# Main.net
KiCad netlist of a schematic drawn in Altium Designer
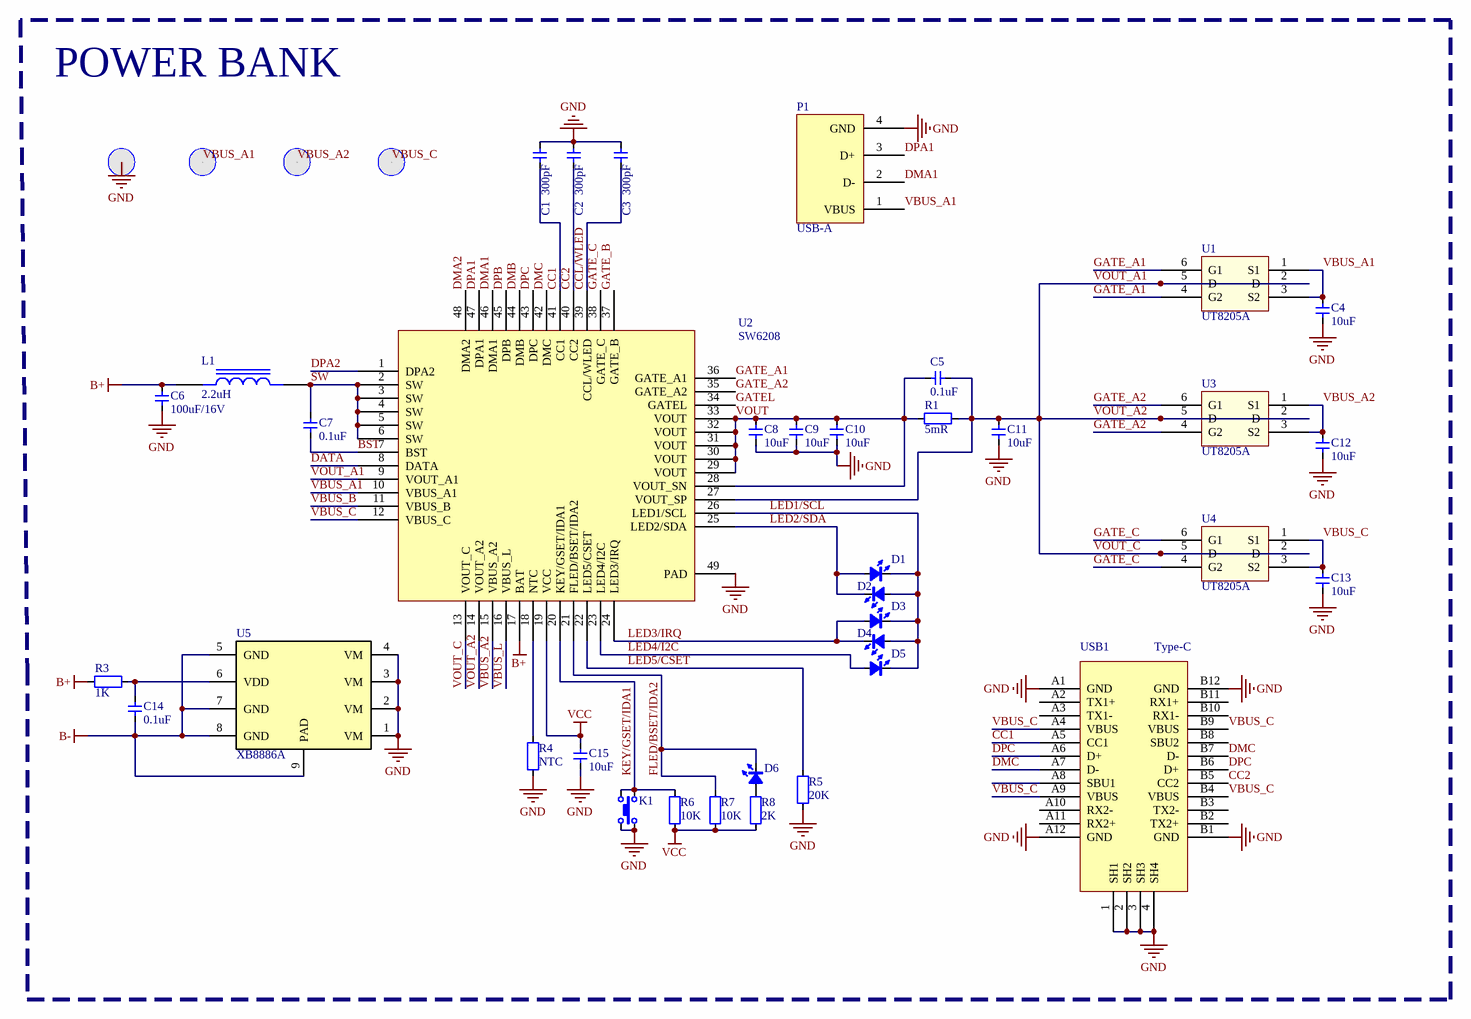
[diagram p0: Main.SchDoc]

(export (version "E")
  (design (tool "Eeschema 10.0.6"))
  (components
    (comp (ref "C1")
      (value "300pF")
      (footprint "CAP_0402")
      (description "Capacitor")
      (libsource (lib "MyPcbLib") (part "电容-0402"))
    )
    (comp (ref "C2")
      (value "300pF")
      (footprint "CAP_0402")
      (description "Capacitor")
      (libsource (lib "MyPcbLib") (part "电容-0402"))
    )
    (comp (ref "C3")
      (value "300pF")
      (footprint "CAP_0402")
      (description "Capacitor")
      (libsource (lib "MyPcbLib") (part "电容-0402"))
    )
    (comp (ref "C4")
      (value "10uF")
      (footprint "0603-CAP")
      (description "Capacitor")
      (libsource (lib "MyPcbLib") (part "电容-0603"))
    )
    (comp (ref "C5")
      (value "0.1uF")
      (footprint "CAP_0402")
      (description "Capacitor")
      (libsource (lib "MyPcbLib") (part "电容-0402"))
    )
    (comp (ref "C6")
      (value "100uF/16V")
      (footprint "1206-CAP")
      (description "Capacitor")
      (libsource (lib "MyPcbLib") (part "电容-1206"))
    )
    (comp (ref "C7")
      (value "0.1uF")
      (footprint "CAP_0402")
      (description "Capacitor")
      (libsource (lib "MyPcbLib") (part "电容-0402"))
    )
    (comp (ref "C8")
      (value "10uF")
      (footprint "0603-CAP")
      (description "Capacitor")
      (libsource (lib "MyPcbLib") (part "电容-0603"))
    )
    (comp (ref "C9")
      (value "10uF")
      (footprint "0603-CAP")
      (description "Capacitor")
      (libsource (lib "MyPcbLib") (part "电容-0603"))
    )
    (comp (ref "C10")
      (value "10uF")
      (footprint "0603-CAP")
      (description "Capacitor")
      (libsource (lib "MyPcbLib") (part "电容-0603"))
    )
    (comp (ref "C11")
      (value "10uF")
      (footprint "0603-CAP")
      (description "Capacitor")
      (libsource (lib "MyPcbLib") (part "电容-0603"))
    )
    (comp (ref "C12")
      (value "10uF")
      (footprint "0603-CAP")
      (description "Capacitor")
      (libsource (lib "MyPcbLib") (part "电容-0603"))
    )
    (comp (ref "C13")
      (value "10uF")
      (footprint "0603-CAP")
      (description "Capacitor")
      (libsource (lib "MyPcbLib") (part "电容-0603"))
    )
    (comp (ref "C14")
      (value "0.1uF")
      (footprint "CAP_0402")
      (description "Capacitor")
      (libsource (lib "MyPcbLib") (part "电容-0402"))
    )
    (comp (ref "C15")
      (value "10uF")
      (footprint "CAP_0402")
      (description "Capacitor")
      (libsource (lib "MyPcbLib") (part "电容-0402"))
    )
    (comp (ref "D1")
      (value "color?")
      (footprint "LED_0402_BLUE")
      (description "LED")
      (libsource (lib "KitSprout") (part "LED_0402"))
    )
    (comp (ref "D2")
      (value "color?")
      (footprint "LED_0402_BLUE")
      (description "LED")
      (libsource (lib "") (part "LED_0402_1"))
    )
    (comp (ref "D3")
      (value "color?")
      (footprint "LED_0402_BLUE")
      (description "LED")
      (libsource (lib "KitSprout") (part "LED_0402"))
    )
    (comp (ref "D4")
      (value "color?")
      (footprint "LED_0402_BLUE")
      (description "LED")
      (libsource (lib "") (part "LED_0402_1"))
    )
    (comp (ref "D5")
      (value "color?")
      (footprint "LED_0402_BLUE")
      (description "LED")
      (libsource (lib "KitSprout") (part "LED_0402"))
    )
    (comp (ref "D6")
      (value "color?")
      (footprint "LED_0402_GREEN")
      (description "LED")
      (libsource (lib "") (part "LED_0402_2"))
    )
    (comp (ref "K1")
      (value "TACT 4P")
      (footprint "ButtonTACT_3.5*3.55_90")
      (description "Button")
      (libsource (lib "KitSprout") (part "ButtonTACT"))
    )
    (comp (ref "L1")
      (value "2.2uH")
      (footprint "mLib:IND_1040")
      (description "Fixed Inductors 4.7uH 30% SMD 1240")
      (fields (field (name "MF") "Bourns") (field (name "MP") "SRR1240-4R7Y"))
      (libsource (lib "mLib") (part "电感-1040"))
    )
    (comp (ref "P1") (value "USB-A") (footprint "USB-Short") (libsource (lib "MyPcbLib") (part "USB-A")))
    (comp (ref "R1")
      (value "5mR")
      (footprint "1206-RES")
      (description "Resistor")
      (libsource (lib "MyPcbLib") (part "电阻-1206"))
    )
    (comp (ref "R3")
      (value "1K")
      (footprint "RES_0402")
      (description "Resistor")
      (libsource (lib "") (part "电阻-0402_1"))
    )
    (comp (ref "R4")
      (value "NTC")
      (footprint "0805-L")
      (description "Resistor")
      (libsource (lib "MyPcbLib") (part "电阻-0805"))
    )
    (comp (ref "R5")
      (value "20K")
      (footprint "RES_0402")
      (description "Resistor")
      (libsource (lib "MyPcbLib") (part "电阻-0402"))
    )
    (comp (ref "R6")
      (value "10K")
      (footprint "RES_0402")
      (description "Resistor")
      (libsource (lib "MyPcbLib") (part "电阻-0402"))
    )
    (comp (ref "R7")
      (value "10K")
      (footprint "RES_0402")
      (description "Resistor")
      (libsource (lib "MyPcbLib") (part "电阻-0402"))
    )
    (comp (ref "R8")
      (value "2K")
      (footprint "RES_0402")
      (description "Resistor")
      (libsource (lib "MyPcbLib") (part "电阻-0402"))
    )
    (comp (ref "T1") (value "测试点") (footprint "TEST_PT") (libsource (lib "MyPcbLib") (part "测试点")))
    (comp (ref "T2") (value "测试点") (footprint "TEST_PT") (libsource (lib "MyPcbLib") (part "测试点")))
    (comp (ref "T3") (value "测试点") (footprint "TEST_PT") (libsource (lib "MyPcbLib") (part "测试点")))
    (comp (ref "T4") (value "测试点") (footprint "TEST_PT") (libsource (lib "MyPcbLib") (part "测试点")))
    (comp (ref "U1") (value "UT8205A") (footprint "SOT23-6") (libsource (lib "mLib") (part "UT8205A")))
    (comp (ref "U2")
      (value "SW6208")
      (footprint "QFN-48_6x6")
      (description "充电宝芯片")
      (libsource (lib "mLib") (part "SW6208"))
    )
    (comp (ref "U3") (value "UT8205A") (footprint "SOT23-6") (libsource (lib "mLib") (part "UT8205A")))
    (comp (ref "U4") (value "UT8205A") (footprint "SOT23-6") (libsource (lib "mLib") (part "UT8205A")))
    (comp (ref "U5")
      (value "XB8886A")
      (footprint "mLib:SO-8-PAD")
      (fields (field (name "MF") "Texas Instruments") (field (name "MP") "NE5532D"))
      (libsource (lib "mLib") (part "XB8886A"))
    )
    (comp (ref "USB1")
      (value "Type-C")
      (footprint "Type-C-TOP")
      (libsource (lib "MyPcbLib") (part "USB-Type-C-TOP"))
    )
  )
  (nets
    (net (code "1") (name "/BST") (class "Default")
      (node (ref "C7") (pin "2") (pinfunction "2_2") (pintype "passive"))
      (node (ref "U2") (pin "7") (pinfunction "BST_7") (pintype "passive"))
    )
    (net (code "2") (name "/CC1") (class "Default")
      (node (ref "C1") (pin "2") (pinfunction "2_2") (pintype "passive"))
      (node (ref "U2") (pin "41") (pinfunction "CC1_41") (pintype "passive"))
      (node (ref "USB1") (pin "A5") (pinfunction "CC1_A5") (pintype "passive"))
    )
    (net (code "3") (name "/CC2") (class "Default")
      (node (ref "C2") (pin "2") (pinfunction "2_2") (pintype "passive"))
      (node (ref "U2") (pin "40") (pinfunction "CC2_40") (pintype "passive"))
      (node (ref "USB1") (pin "B5") (pinfunction "CC2_B5") (pintype "passive"))
    )
    (net (code "4") (name "/CCL{slash}WLED") (class "Default")
      (node (ref "C3") (pin "2") (pinfunction "2_2") (pintype "passive"))
      (node (ref "U2") (pin "39") (pinfunction "CCL/WLED_39") (pintype "passive"))
    )
    (net (code "5") (name "/DATA") (class "Default")
      (node (ref "U2") (pin "8") (pinfunction "DATA_8") (pintype "passive"))
    )
    (net (code "6") (name "/DMA1") (class "Default")
      (node (ref "P1") (pin "2") (pinfunction "D-_2") (pintype "passive"))
      (node (ref "U2") (pin "46") (pinfunction "DMA1_46") (pintype "passive"))
    )
    (net (code "7") (name "/DMA2") (class "Default")
      (node (ref "U2") (pin "48") (pinfunction "DMA2_48") (pintype "passive"))
    )
    (net (code "8") (name "/DMB") (class "Default")
      (node (ref "U2") (pin "44") (pinfunction "DMB_44") (pintype "passive"))
    )
    (net (code "9") (name "/DMC") (class "Default")
      (node (ref "U2") (pin "42") (pinfunction "DMC_42") (pintype "passive"))
      (node (ref "USB1") (pin "A7") (pinfunction "D-_A7") (pintype "passive"))
      (node (ref "USB1") (pin "B7") (pinfunction "D-_B7") (pintype "passive"))
    )
    (net (code "10") (name "/DPA1") (class "Default")
      (node (ref "P1") (pin "3") (pinfunction "D+_3") (pintype "passive"))
      (node (ref "U2") (pin "47") (pinfunction "DPA1_47") (pintype "passive"))
    )
    (net (code "11") (name "/DPA2") (class "Default")
      (node (ref "U2") (pin "1") (pinfunction "DPA2_1") (pintype "passive"))
    )
    (net (code "12") (name "/DPB") (class "Default")
      (node (ref "U2") (pin "45") (pinfunction "DPB_45") (pintype "passive"))
    )
    (net (code "13") (name "/DPC") (class "Default")
      (node (ref "U2") (pin "43") (pinfunction "DPC_43") (pintype "passive"))
      (node (ref "USB1") (pin "A6") (pinfunction "D+_A6") (pintype "passive"))
      (node (ref "USB1") (pin "B6") (pinfunction "D+_B6") (pintype "passive"))
    )
    (net (code "14") (name "/FLED{slash}BSET{slash}IDA2") (class "Default")
      (node (ref "D6") (pin "2") (pinfunction "K_2") (pintype "passive"))
      (node (ref "R7") (pin "2") (pinfunction "2_2") (pintype "passive"))
      (node (ref "U2") (pin "21") (pinfunction "FLED/BSET/IDA2_21") (pintype "passive"))
    )
    (net (code "15") (name "/GATEL") (class "Default")
      (node (ref "U2") (pin "34") (pinfunction "GATEL_34") (pintype "passive"))
    )
    (net (code "16") (name "/GATE_A1") (class "Default")
      (node (ref "U1") (pin "4") (pinfunction "G2_4") (pintype "passive"))
      (node (ref "U1") (pin "6") (pinfunction "G1_6") (pintype "passive"))
      (node (ref "U2") (pin "36") (pinfunction "GATE_A1_36") (pintype "passive"))
    )
    (net (code "17") (name "/GATE_A2") (class "Default")
      (node (ref "U2") (pin "35") (pinfunction "GATE_A2_35") (pintype "passive"))
      (node (ref "U3") (pin "4") (pinfunction "G2_4") (pintype "passive"))
      (node (ref "U3") (pin "6") (pinfunction "G1_6") (pintype "passive"))
    )
    (net (code "18") (name "/GATE_B") (class "Default")
      (node (ref "U2") (pin "37") (pinfunction "GATE_B_37") (pintype "passive"))
    )
    (net (code "19") (name "/GATE_C") (class "Default")
      (node (ref "U2") (pin "38") (pinfunction "GATE_C_38") (pintype "passive"))
      (node (ref "U4") (pin "4") (pinfunction "G2_4") (pintype "passive"))
      (node (ref "U4") (pin "6") (pinfunction "G1_6") (pintype "passive"))
    )
    (net (code "20") (name "/KEY{slash}GSET{slash}IDA1") (class "Default")
      (node (ref "K1") (pin "2") (pinfunction "2_2") (pintype "passive"))
      (node (ref "K1") (pin "4") (pinfunction "4_4") (pintype "passive"))
      (node (ref "R6") (pin "2") (pinfunction "2_2") (pintype "passive"))
      (node (ref "U2") (pin "20") (pinfunction "KEY/GSET/IDA1_20") (pintype "passive"))
    )
    (net (code "21") (name "/LED1{slash}SCL") (class "Default")
      (node (ref "D1") (pin "2") (pinfunction "K_2") (pintype "passive"))
      (node (ref "D2") (pin "1") (pinfunction "A_1") (pintype "passive"))
      (node (ref "D3") (pin "2") (pinfunction "K_2") (pintype "passive"))
      (node (ref "D4") (pin "1") (pinfunction "A_1") (pintype "passive"))
      (node (ref "D5") (pin "2") (pinfunction "K_2") (pintype "passive"))
      (node (ref "U2") (pin "26") (pinfunction "LED1/SCL_26") (pintype "passive"))
    )
    (net (code "22") (name "/LED2{slash}SDA") (class "Default")
      (node (ref "D1") (pin "1") (pinfunction "A_1") (pintype "passive"))
      (node (ref "D2") (pin "2") (pinfunction "K_2") (pintype "passive"))
      (node (ref "U2") (pin "25") (pinfunction "LED2/SDA_25") (pintype "passive"))
    )
    (net (code "23") (name "/LED3{slash}IRQ") (class "Default")
      (node (ref "D3") (pin "1") (pinfunction "A_1") (pintype "passive"))
      (node (ref "D4") (pin "2") (pinfunction "K_2") (pintype "passive"))
      (node (ref "U2") (pin "24") (pinfunction "LED3/IRQ_24") (pintype "passive"))
    )
    (net (code "24") (name "/LED4{slash}I2C") (class "Default")
      (node (ref "D5") (pin "1") (pinfunction "A_1") (pintype "passive"))
      (node (ref "U2") (pin "23") (pinfunction "LED4/I2C_23") (pintype "passive"))
    )
    (net (code "25") (name "/LED5{slash}CSET") (class "Default")
      (node (ref "R5") (pin "2") (pinfunction "2_2") (pintype "passive"))
      (node (ref "U2") (pin "22") (pinfunction "LED5/CSET_22") (pintype "passive"))
    )
    (net (code "26") (name "/SW") (class "Default")
      (node (ref "C7") (pin "1") (pinfunction "1_1") (pintype "passive"))
      (node (ref "L1") (pin "2") (pinfunction "2_2") (pintype "passive"))
      (node (ref "U2") (pin "2") (pinfunction "SW_2") (pintype "passive"))
      (node (ref "U2") (pin "3") (pinfunction "SW_3") (pintype "passive"))
      (node (ref "U2") (pin "4") (pinfunction "SW_4") (pintype "passive"))
      (node (ref "U2") (pin "5") (pinfunction "SW_5") (pintype "passive"))
      (node (ref "U2") (pin "6") (pinfunction "SW_6") (pintype "passive"))
    )
    (net (code "27") (name "/VBUS_A1") (class "Default")
      (node (ref "C4") (pin "2") (pinfunction "2_2") (pintype "passive"))
      (node (ref "P1") (pin "1") (pinfunction "VBUS_1") (pintype "passive"))
      (node (ref "T2") (pin "0") (pinfunction "0_0") (pintype "passive"))
      (node (ref "U1") (pin "1") (pinfunction "S1_1") (pintype "passive"))
      (node (ref "U1") (pin "3") (pinfunction "S2_3") (pintype "passive"))
      (node (ref "U2") (pin "10") (pinfunction "VBUS_A1_10") (pintype "passive"))
    )
    (net (code "28") (name "/VBUS_A2") (class "Default")
      (node (ref "C12") (pin "2") (pinfunction "2_2") (pintype "passive"))
      (node (ref "T3") (pin "0") (pinfunction "0_0") (pintype "passive"))
      (node (ref "U2") (pin "15") (pinfunction "VBUS_A2_15") (pintype "passive"))
      (node (ref "U3") (pin "1") (pinfunction "S1_1") (pintype "passive"))
      (node (ref "U3") (pin "3") (pinfunction "S2_3") (pintype "passive"))
    )
    (net (code "29") (name "/VBUS_B") (class "Default")
      (node (ref "U2") (pin "11") (pinfunction "VBUS_B_11") (pintype "passive"))
    )
    (net (code "30") (name "/VBUS_C") (class "Default")
      (node (ref "C13") (pin "2") (pinfunction "2_2") (pintype "passive"))
      (node (ref "T4") (pin "0") (pinfunction "0_0") (pintype "passive"))
      (node (ref "U2") (pin "12") (pinfunction "VBUS_C_12") (pintype "passive"))
      (node (ref "U4") (pin "1") (pinfunction "S1_1") (pintype "passive"))
      (node (ref "U4") (pin "3") (pinfunction "S2_3") (pintype "passive"))
      (node (ref "USB1") (pin "A4") (pinfunction "VBUS_A4") (pintype "passive"))
      (node (ref "USB1") (pin "A9") (pinfunction "VBUS_A9") (pintype "passive"))
      (node (ref "USB1") (pin "B4") (pinfunction "VBUS_B4") (pintype "passive"))
      (node (ref "USB1") (pin "B9") (pinfunction "VBUS_B9") (pintype "passive"))
    )
    (net (code "31") (name "/VBUS_L") (class "Default")
      (node (ref "U2") (pin "16") (pinfunction "VBUS_L_16") (pintype "passive"))
    )
    (net (code "32") (name "/VOUT") (class "Default")
      (node (ref "C10") (pin "2") (pinfunction "2_2") (pintype "passive"))
      (node (ref "C5") (pin "1") (pinfunction "1_1") (pintype "passive"))
      (node (ref "C8") (pin "2") (pinfunction "2_2") (pintype "passive"))
      (node (ref "C9") (pin "2") (pinfunction "2_2") (pintype "passive"))
      (node (ref "R1") (pin "1") (pinfunction "1_1") (pintype "passive"))
      (node (ref "U2") (pin "28") (pinfunction "VOUT_SN_28") (pintype "passive"))
      (node (ref "U2") (pin "29") (pinfunction "VOUT_29") (pintype "passive"))
      (node (ref "U2") (pin "30") (pinfunction "VOUT_30") (pintype "passive"))
      (node (ref "U2") (pin "31") (pinfunction "VOUT_31") (pintype "passive"))
      (node (ref "U2") (pin "32") (pinfunction "VOUT_32") (pintype "passive"))
      (node (ref "U2") (pin "33") (pinfunction "VOUT_33") (pintype "passive"))
    )
    (net (code "33") (name "/VOUT_A1") (class "Default")
      (node (ref "C11") (pin "2") (pinfunction "2_2") (pintype "passive"))
      (node (ref "C5") (pin "2") (pinfunction "2_2") (pintype "passive"))
      (node (ref "R1") (pin "2") (pinfunction "2_2") (pintype "passive"))
      (node (ref "U1") (pin "2") (pinfunction "D_2") (pintype "passive"))
      (node (ref "U1") (pin "5") (pinfunction "D_5") (pintype "passive"))
      (node (ref "U2") (pin "13") (pinfunction "VOUT_C_13") (pintype "passive"))
      (node (ref "U2") (pin "14") (pinfunction "VOUT_A2_14") (pintype "passive"))
      (node (ref "U2") (pin "27") (pinfunction "VOUT_SP_27") (pintype "passive"))
      (node (ref "U2") (pin "9") (pinfunction "VOUT_A1_9") (pintype "passive"))
      (node (ref "U3") (pin "2") (pinfunction "D_2") (pintype "passive"))
      (node (ref "U3") (pin "5") (pinfunction "D_5") (pintype "passive"))
      (node (ref "U4") (pin "2") (pinfunction "D_2") (pintype "passive"))
      (node (ref "U4") (pin "5") (pinfunction "D_5") (pintype "passive"))
    )
    (net (code "34") (name "B+") (class "Default")
      (node (ref "C6") (pin "2") (pinfunction "2_2") (pintype "passive"))
      (node (ref "L1") (pin "1") (pinfunction "1_1") (pintype "passive"))
      (node (ref "R3") (pin "2") (pinfunction "2_2") (pintype "passive"))
      (node (ref "U2") (pin "17") (pinfunction "BAT_17") (pintype "passive"))
    )
    (net (code "35") (name "B-") (class "Default")
      (node (ref "C14") (pin "2") (pinfunction "2_2") (pintype "passive"))
      (node (ref "U5") (pin "5") (pinfunction "GND_5") (pintype "passive"))
      (node (ref "U5") (pin "7") (pinfunction "GND_7") (pintype "passive"))
      (node (ref "U5") (pin "8") (pinfunction "GND_8") (pintype "passive"))
      (node (ref "U5") (pin "9") (pinfunction "PAD_9") (pintype "passive"))
    )
    (net (code "36") (name "GND") (class "Default")
      (node (ref "C1") (pin "1") (pinfunction "1_1") (pintype "passive"))
      (node (ref "C10") (pin "1") (pinfunction "1_1") (pintype "passive"))
      (node (ref "C11") (pin "1") (pinfunction "1_1") (pintype "passive"))
      (node (ref "C12") (pin "1") (pinfunction "1_1") (pintype "passive"))
      (node (ref "C13") (pin "1") (pinfunction "1_1") (pintype "passive"))
      (node (ref "C15") (pin "2") (pinfunction "2_2") (pintype "passive"))
      (node (ref "C2") (pin "1") (pinfunction "1_1") (pintype "passive"))
      (node (ref "C3") (pin "1") (pinfunction "1_1") (pintype "passive"))
      (node (ref "C4") (pin "1") (pinfunction "1_1") (pintype "passive"))
      (node (ref "C6") (pin "1") (pinfunction "1_1") (pintype "passive"))
      (node (ref "C8") (pin "1") (pinfunction "1_1") (pintype "passive"))
      (node (ref "C9") (pin "1") (pinfunction "1_1") (pintype "passive"))
      (node (ref "K1") (pin "1") (pinfunction "1_1") (pintype "passive"))
      (node (ref "K1") (pin "3") (pinfunction "3_3") (pintype "passive"))
      (node (ref "P1") (pin "4") (pinfunction "GND_4") (pintype "passive"))
      (node (ref "R4") (pin "1") (pinfunction "1_1") (pintype "passive"))
      (node (ref "R5") (pin "1") (pinfunction "1_1") (pintype "passive"))
      (node (ref "T1") (pin "0") (pinfunction "0_0") (pintype "passive"))
      (node (ref "U2") (pin "49") (pinfunction "PAD_49") (pintype "passive"))
      (node (ref "U5") (pin "1") (pinfunction "VM_1") (pintype "passive"))
      (node (ref "U5") (pin "2") (pinfunction "VM_2") (pintype "passive"))
      (node (ref "U5") (pin "3") (pinfunction "VM_3") (pintype "passive"))
      (node (ref "U5") (pin "4") (pinfunction "VM_4") (pintype "passive"))
      (node (ref "USB1") (pin "1") (pinfunction "SH1_1") (pintype "passive"))
      (node (ref "USB1") (pin "2") (pinfunction "SH2_2") (pintype "passive"))
      (node (ref "USB1") (pin "3") (pinfunction "SH3_3") (pintype "passive"))
      (node (ref "USB1") (pin "4") (pinfunction "SH4_4") (pintype "passive"))
      (node (ref "USB1") (pin "A1") (pinfunction "GND_A1") (pintype "passive"))
      (node (ref "USB1") (pin "A12") (pinfunction "GND_A12") (pintype "passive"))
      (node (ref "USB1") (pin "B1") (pinfunction "GND_B1") (pintype "passive"))
      (node (ref "USB1") (pin "B12") (pinfunction "GND_B12") (pintype "passive"))
    )
    (net (code "37") (name "Net-(D6-A)") (class "Default")
      (node (ref "D6") (pin "1") (pinfunction "A_1") (pintype "passive"))
      (node (ref "R8") (pin "2") (pinfunction "2_2") (pintype "passive"))
    )
    (net (code "38") (name "Net-(U2-NTC)") (class "Default")
      (node (ref "R4") (pin "2") (pinfunction "2_2") (pintype "passive"))
      (node (ref "U2") (pin "18") (pinfunction "NTC_18") (pintype "passive"))
    )
    (net (code "39") (name "Net-(U5-VDD)") (class "Default")
      (node (ref "C14") (pin "1") (pinfunction "1_1") (pintype "passive"))
      (node (ref "R3") (pin "1") (pinfunction "1_1") (pintype "passive"))
      (node (ref "U5") (pin "6") (pinfunction "VDD_6") (pintype "passive"))
    )
    (net (code "40") (name "VCC") (class "Default")
      (node (ref "C15") (pin "1") (pinfunction "1_1") (pintype "passive"))
      (node (ref "R6") (pin "1") (pinfunction "1_1") (pintype "passive"))
      (node (ref "R7") (pin "1") (pinfunction "1_1") (pintype "passive"))
      (node (ref "R8") (pin "1") (pinfunction "1_1") (pintype "passive"))
      (node (ref "U2") (pin "19") (pinfunction "VCC_19") (pintype "passive"))
    )
    (net (code "41") (name "unconnected-(USB1-RX1+-PadB11)") (class "Default")
      (node (ref "USB1") (pin "B11") (pinfunction "RX1+_B11") (pintype "passive"))
    )
    (net (code "42") (name "unconnected-(USB1-RX1--PadB10)") (class "Default")
      (node (ref "USB1") (pin "B10") (pinfunction "RX1-_B10") (pintype "passive"))
    )
    (net (code "43") (name "unconnected-(USB1-RX2+-PadA11)") (class "Default")
      (node (ref "USB1") (pin "A11") (pinfunction "RX2+_A11") (pintype "passive"))
    )
    (net (code "44") (name "unconnected-(USB1-RX2--PadA10)") (class "Default")
      (node (ref "USB1") (pin "A10") (pinfunction "RX2-_A10") (pintype "passive"))
    )
    (net (code "45") (name "unconnected-(USB1-SBU1-PadA8)") (class "Default")
      (node (ref "USB1") (pin "A8") (pinfunction "SBU1_A8") (pintype "passive"))
    )
    (net (code "46") (name "unconnected-(USB1-SBU2-PadB8)") (class "Default")
      (node (ref "USB1") (pin "B8") (pinfunction "SBU2_B8") (pintype "passive"))
    )
    (net (code "47") (name "unconnected-(USB1-TX1+-PadA2)") (class "Default")
      (node (ref "USB1") (pin "A2") (pinfunction "TX1+_A2") (pintype "passive"))
    )
    (net (code "48") (name "unconnected-(USB1-TX1--PadA3)") (class "Default")
      (node (ref "USB1") (pin "A3") (pinfunction "TX1-_A3") (pintype "passive"))
    )
    (net (code "49") (name "unconnected-(USB1-TX2+-PadB2)") (class "Default")
      (node (ref "USB1") (pin "B2") (pinfunction "TX2+_B2") (pintype "passive"))
    )
    (net (code "50") (name "unconnected-(USB1-TX2--PadB3)") (class "Default")
      (node (ref "USB1") (pin "B3") (pinfunction "TX2-_B3") (pintype "passive"))
    )
  )
)
